# ADIS_Teensy_Arduino_Breakout_RevD.net
KiCad netlist of a schematic drawn in EAGLE
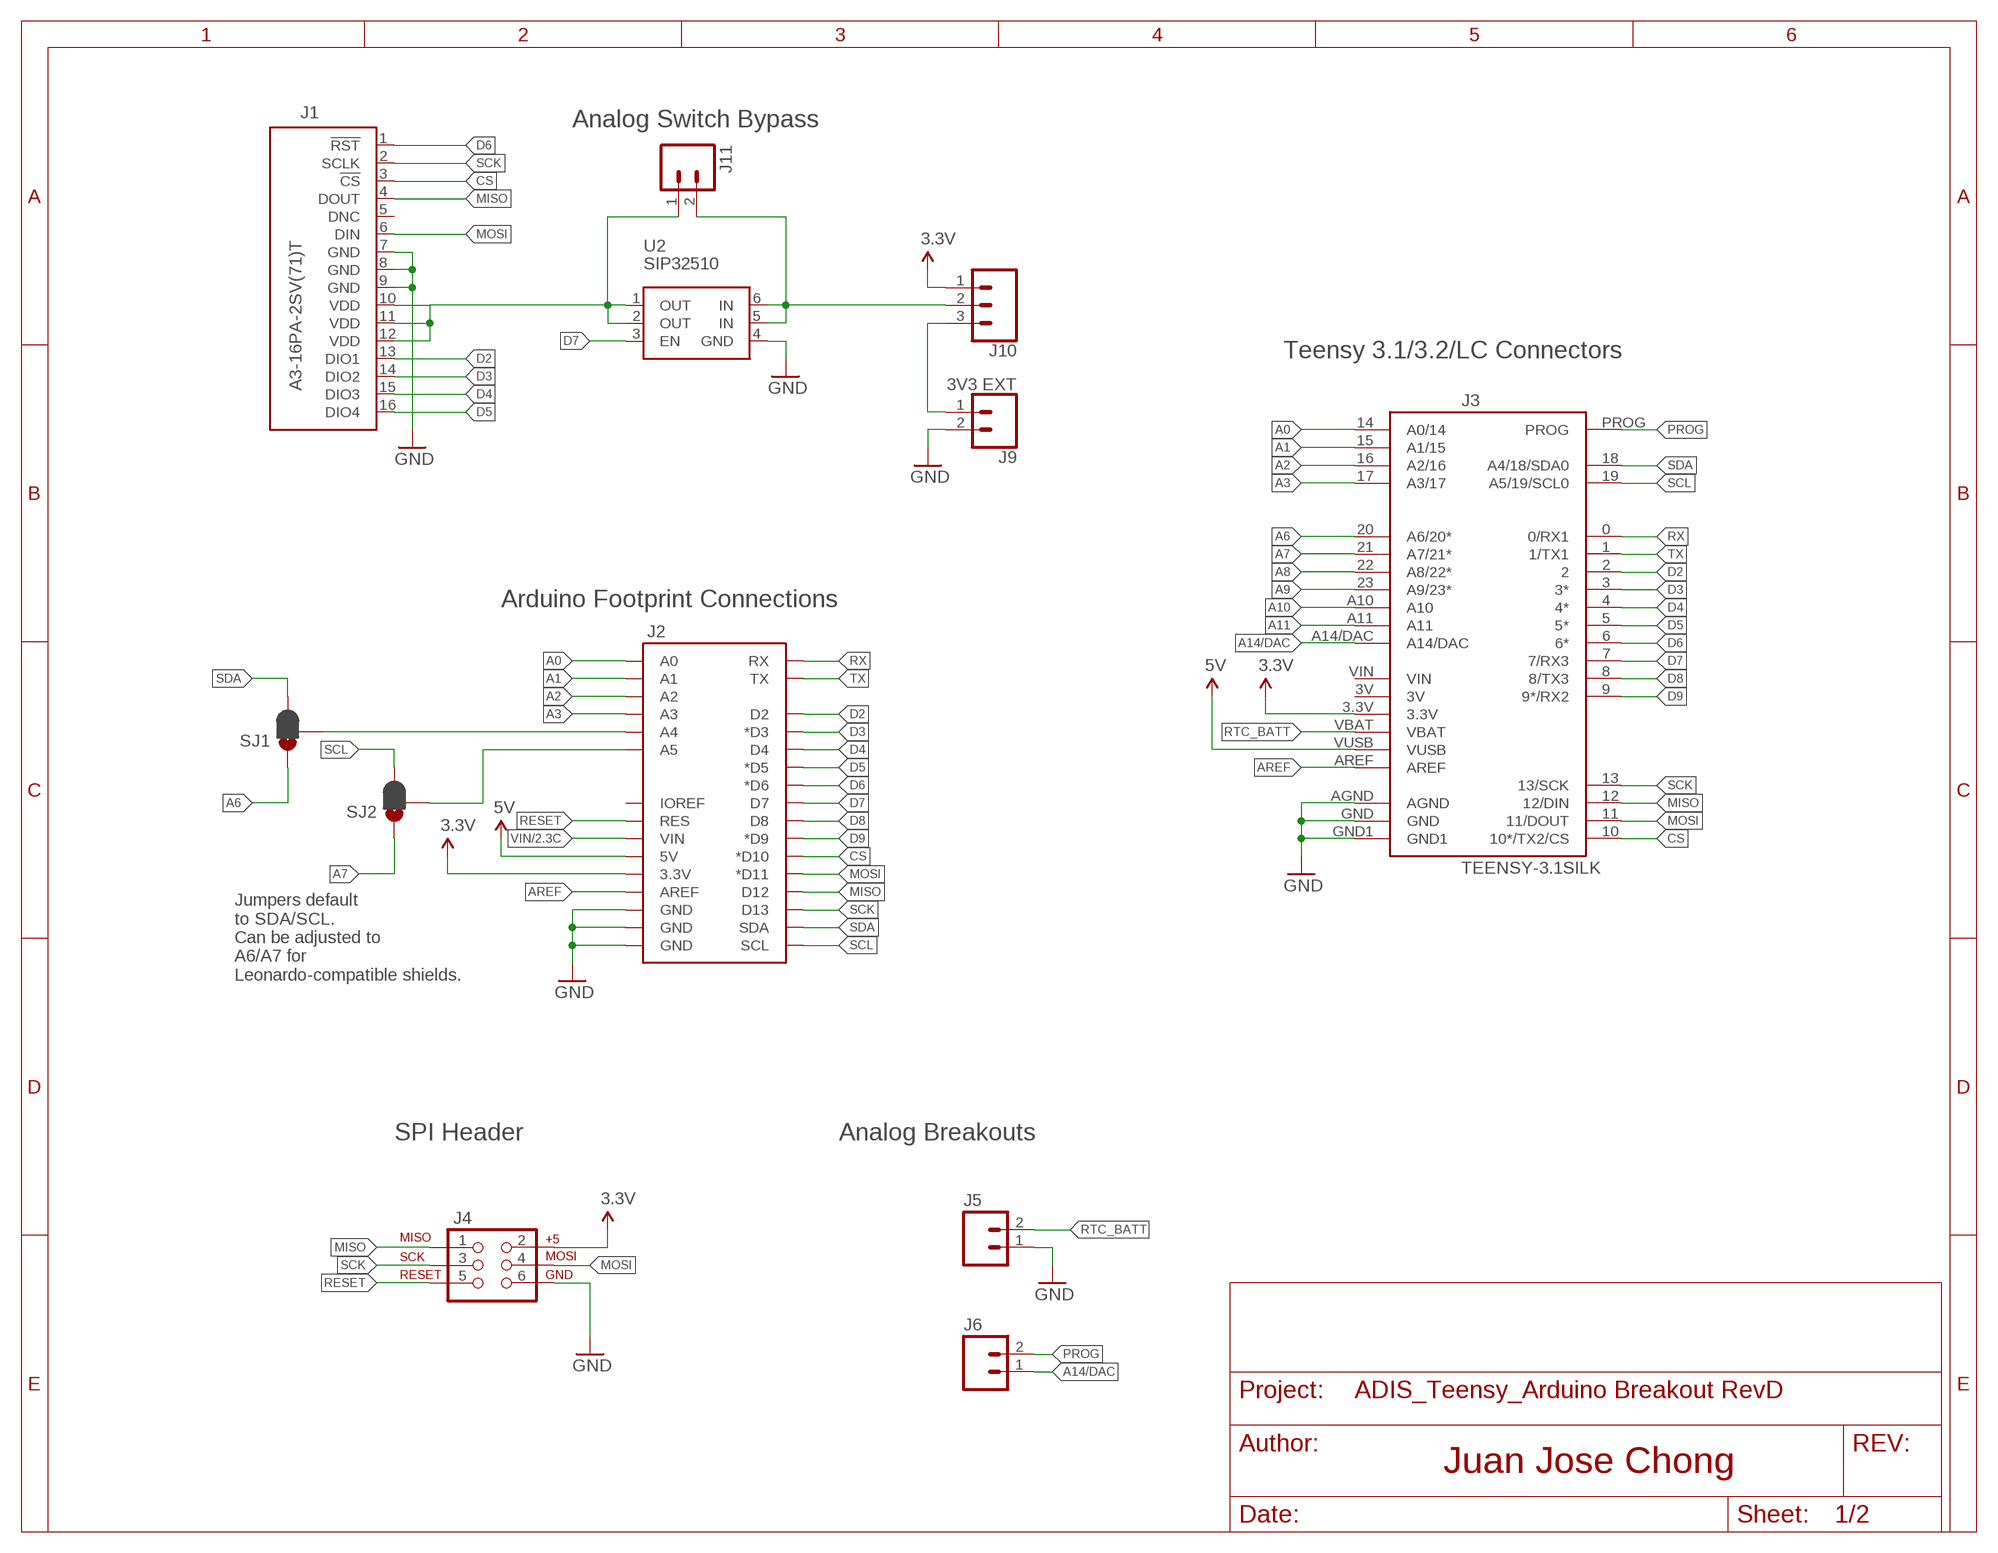
[diagram p0: schematic, sheet 1]
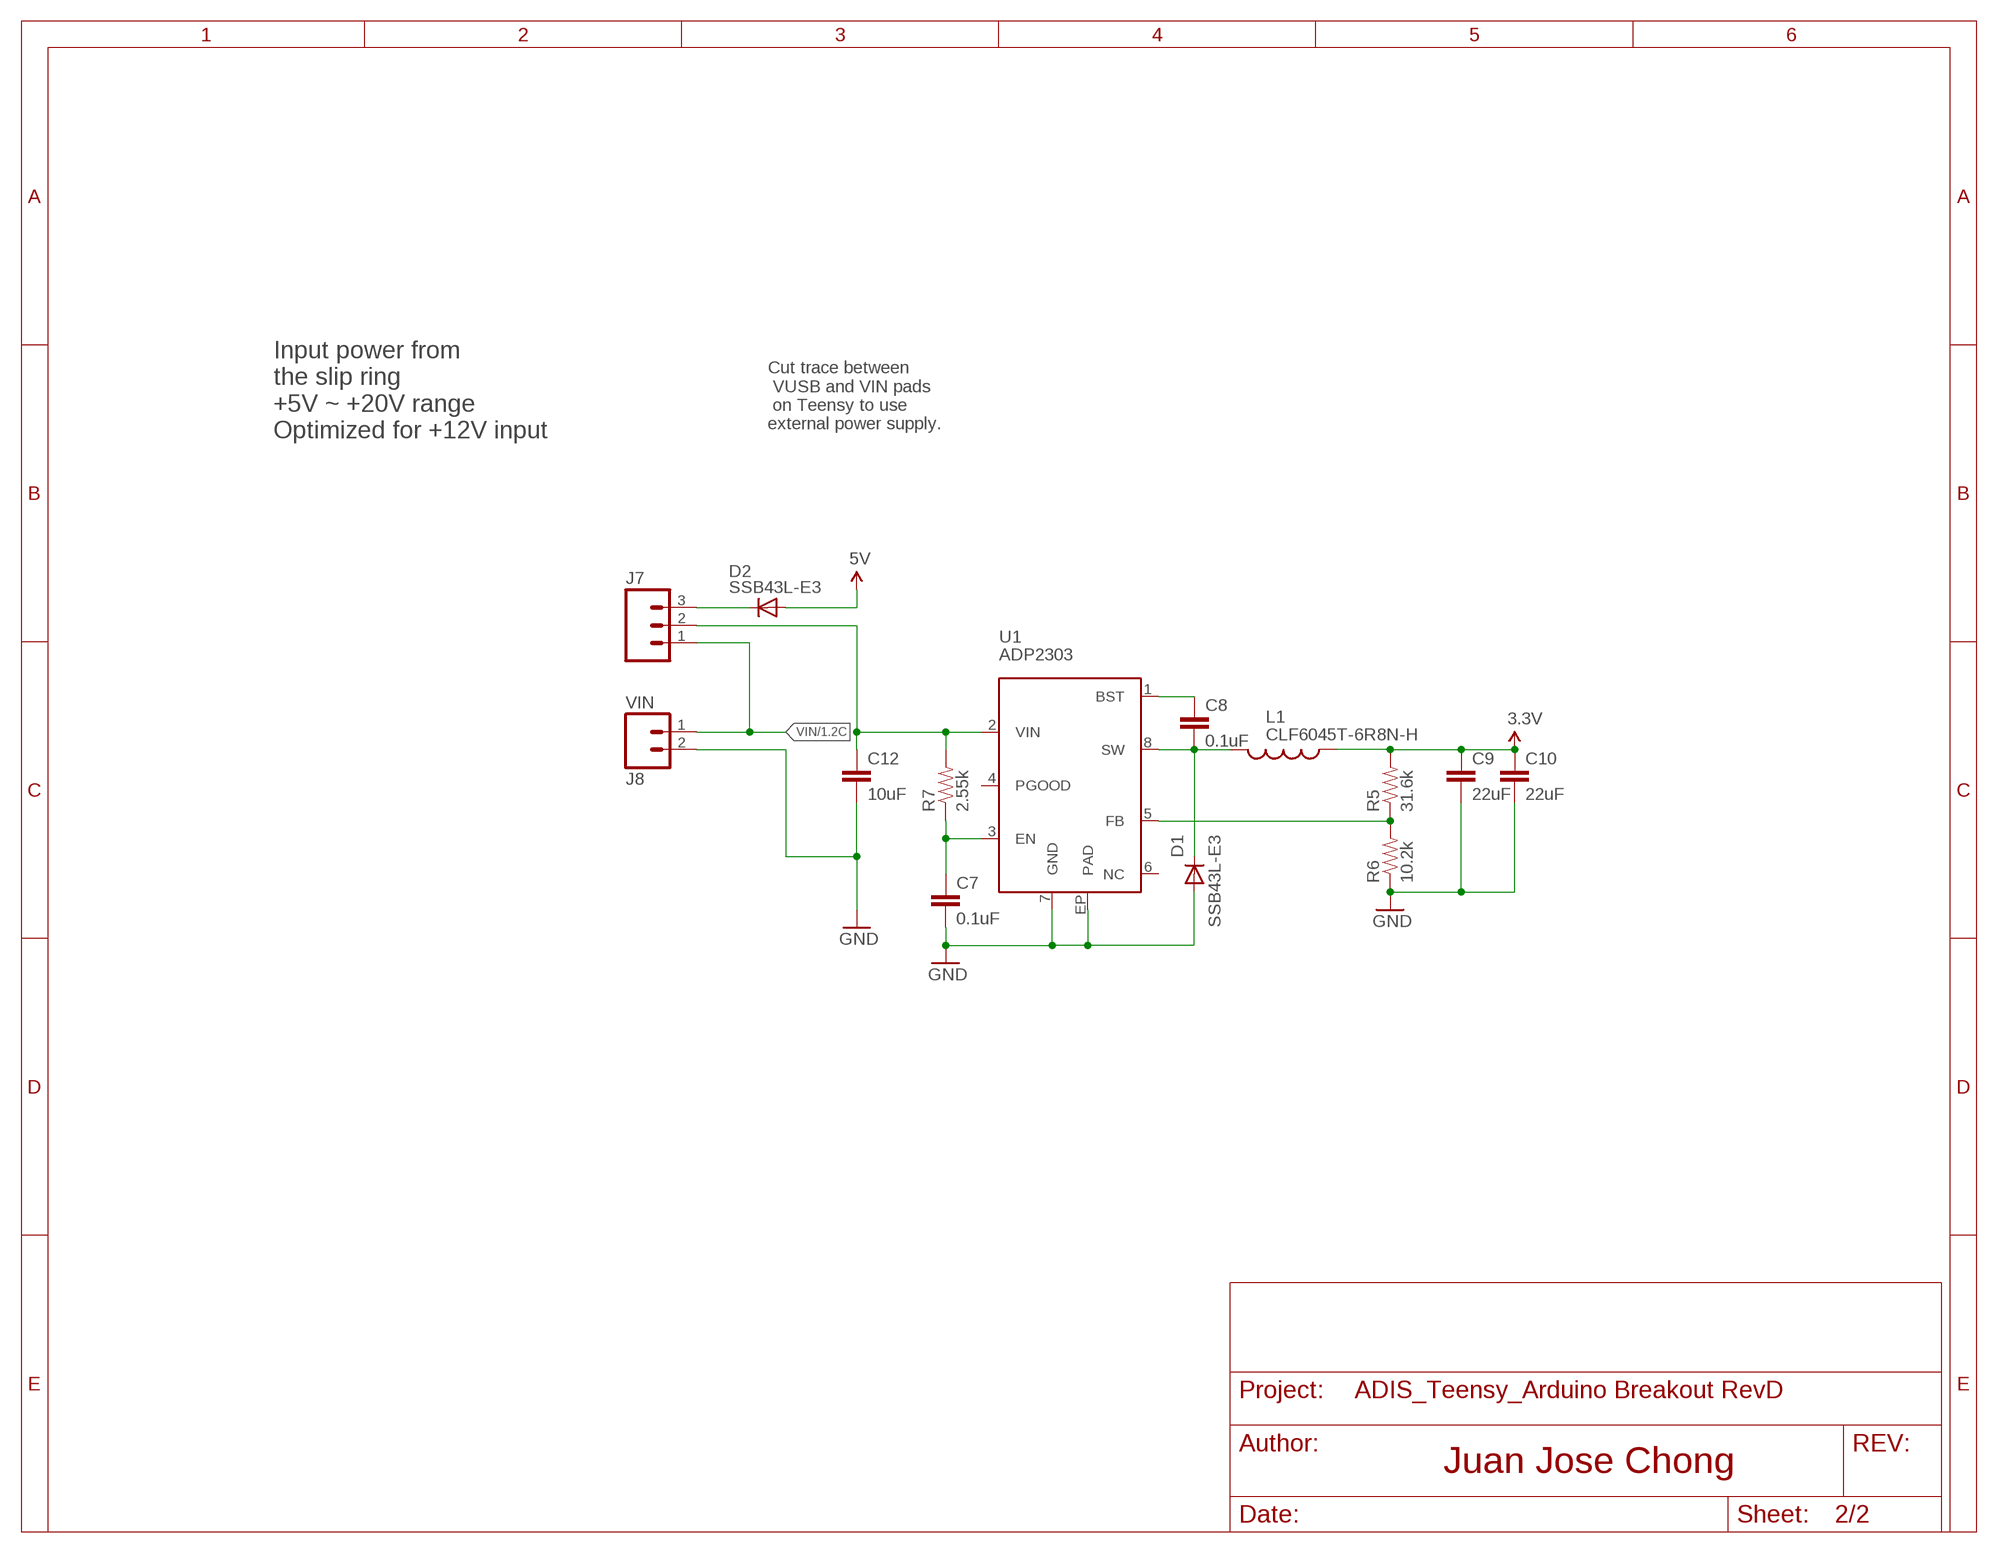
[diagram p1: schematic, sheet 2]

(export (version "E")
  (design (tool "Eeschema 10.0.6"))
  (components
    (comp (ref "J1")
      (value "A3-16PA-2SV(71)T")
      (footprint "eagle-import:A3-16PA-2SV(71)-TOP")
      (fields (field (name "PARTNO") "A3-16PA-2SV(71)"))
      (libsource (lib "eagle-import") (part "A3-16PA-2SV(71)T"))
    )
    (comp (ref "J2")
      (value "ARDUINO_R3_SHIELDUNO_R3_SHIELD_HOLES")
      (footprint "eagle-import:UNO_R3_SHIELD_HOLES")
      (libsource (lib "eagle-import") (part "ARDUINO_R3_SHIELDUNO_R3_SHIELD_HOLES"))
    )
    (comp (ref "J3")
      (value "TEENSY-3.1SILK")
      (footprint "eagle-import:TEENSY-3.1")
      (fields (field (name "PARTNO") "TEENSY32"))
      (libsource (lib "eagle-import") (part "TEENSY-3.1SILK"))
    )
    (comp (ref "J4")
      (value "AVR_SPI_PRG_6PTH")
      (footprint "eagle-import:2X3")
      (fields (field (name "PARTNO") "M20-9720345"))
      (libsource (lib "eagle-import") (part "AVR_SPI_PRG_6PTH"))
    )
    (comp (ref "J5")
      (value "M02PTH")
      (footprint "eagle-import:1X02@1")
      (libsource (lib "eagle-import") (part "M02PTH"))
    )
    (comp (ref "J6")
      (value "M02PTH")
      (footprint "eagle-import:1X02@1")
      (libsource (lib "eagle-import") (part "M02PTH"))
    )
    (comp (ref "J9")
      (value "3V3 EXT")
      (footprint "eagle-import:SCREWTERMINAL-3.5MM-2")
      (fields (field (name "PARTNO") "20020327-C021B01LF"))
      (libsource (lib "eagle-import") (part "CONN_023.5MM"))
    )
    (comp (ref "J10")
      (value "CONN_03")
      (footprint "eagle-import:1X03")
      (fields (field (name "PARTNO") "68000-103HLF"))
      (libsource (lib "eagle-import") (part "CONN_03"))
    )
    (comp (ref "J11")
      (value "M02PTH")
      (footprint "eagle-import:1X02@1")
      (libsource (lib "eagle-import") (part "M02PTH"))
    )
    (comp (ref "SJ1")
      (value "JUMPER-PAD-3-2OF3_NC_BY_PASTE")
      (footprint "eagle-import:PAD-JUMPER-3-2OF3_NC_BY_PASTE_YES_SILK_FULL_BOX")
      (libsource (lib "eagle-import") (part "JUMPER-PAD-3-2OF3_NC_BY_PASTE"))
    )
    (comp (ref "SJ2")
      (value "JUMPER-PAD-3-2OF3_NC_BY_PASTE")
      (footprint "eagle-import:PAD-JUMPER-3-2OF3_NC_BY_PASTE_YES_SILK_FULL_BOX")
      (libsource (lib "eagle-import") (part "JUMPER-PAD-3-2OF3_NC_BY_PASTE"))
    )
    (comp (ref "U2")
      (value "SIP32510")
      (footprint "eagle-import:SOT23-6")
      (fields (field (name "PARTNO") "SIP32510DT-T1-GE3"))
      (libsource (lib "eagle-import") (part "SIP32510"))
    )
    (comp (ref "C7")
      (value "0.1uF")
      (footprint "eagle-import:0603-CAP")
      (fields (field (name "PARTNO") "CL10B104KB8NNNC"))
      (libsource (lib "eagle-import") (part "CAP0603-CAP"))
    )
    (comp (ref "C8")
      (value "0.1uF")
      (footprint "eagle-import:0603-CAP")
      (fields (field (name "PARTNO") "CL10B104KB8NNNC"))
      (libsource (lib "eagle-import") (part "CAP0603-CAP"))
    )
    (comp (ref "C9")
      (value "22uF")
      (footprint "eagle-import:1210")
      (fields (field (name "PARTNO") "TLJA476M010R0600"))
      (libsource (lib "eagle-import") (part "CAP1210"))
    )
    (comp (ref "C10")
      (value "22uF")
      (footprint "eagle-import:1210")
      (fields (field (name "PARTNO") "TLJA476M010R0600"))
      (libsource (lib "eagle-import") (part "CAP1210"))
    )
    (comp (ref "C12")
      (value "10uF")
      (footprint "eagle-import:1206")
      (fields (field (name "PARTNO") "TLJA476M010R0600"))
      (libsource (lib "eagle-import") (part "CAP1206"))
    )
    (comp (ref "D1")
      (value "SSB43L-E3")
      (footprint "eagle-import:DO214AA")
      (fields (field (name "PARTNO") "SSB43L-E3/52T"))
      (libsource (lib "eagle-import") (part "DIODE-DO214AA"))
    )
    (comp (ref "D2")
      (value "SSB43L-E3")
      (footprint "eagle-import:DO214AA")
      (fields (field (name "PARTNO") "SSB43L-E3/52T"))
      (libsource (lib "eagle-import") (part "DIODE-DO214AA"))
    )
    (comp (ref "J7")
      (value "M03PTH")
      (footprint "eagle-import:1X03@1")
      (fields (field (name "PARTNO") "68000-103HLF"))
      (libsource (lib "eagle-import") (part "M03PTH"))
    )
    (comp (ref "J8")
      (value "VIN")
      (footprint "eagle-import:SCREWTERMINAL-3.5MM-2@1")
      (fields (field (name "PARTNO") "20020327-C021B01LF"))
      (libsource (lib "eagle-import") (part "M023.5MM"))
    )
    (comp (ref "L1")
      (value "CLF6045T-6R8N-H")
      (footprint "eagle-import:CLF6045-H")
      (libsource (lib "eagle-import") (part "CLF6045T-6R8N-H"))
    )
    (comp (ref "R5")
      (value "31.6k")
      (footprint "eagle-import:0603-RES")
      (fields (field (name "PARTNO") "ERJ-3EKF3162V"))
      (libsource (lib "eagle-import") (part "RESISTOR0603-RES"))
    )
    (comp (ref "R6")
      (value "10.2k")
      (footprint "eagle-import:0603-RES")
      (fields (field (name "PARTNO") "ERJ-3EKF1022V"))
      (libsource (lib "eagle-import") (part "RESISTOR0603-RES"))
    )
    (comp (ref "R7")
      (value "2.55k")
      (footprint "eagle-import:0603-RES")
      (fields (field (name "PARTNO") "ERJ-3EKF2551V"))
      (libsource (lib "eagle-import") (part "RESISTOR0603-RES"))
    )
    (comp (ref "U1")
      (value "ADP2303")
      (footprint "eagle-import:SOIC-8-PAD")
      (fields (field (name "PARTNO") "ADP2303ARDZ"))
      (libsource (lib "eagle-import") (part "ADP2303"))
    )
  )
  (nets
    (net (code "1") (name "3.3V") (class "Default")
      (node (ref "C10") (pin "1") (pinfunction "1_1") (pintype "passive"))
      (node (ref "C9") (pin "1") (pinfunction "1_1") (pintype "passive"))
      (node (ref "J10") (pin "1") (pinfunction "1_1") (pintype "passive"))
      (node (ref "J2") (pin "3.3V") (pinfunction "3.3V_3.3V") (pintype "bidirectional"))
      (node (ref "J3") (pin "3.3V") (pinfunction "3.3V_3.3V") (pintype "bidirectional"))
      (node (ref "J4") (pin "2") (pinfunction "2_2") (pintype "passive"))
      (node (ref "L1") (pin "P$1") (pinfunction "1_P$1") (pintype "passive"))
      (node (ref "R5") (pin "2") (pinfunction "2_2") (pintype "passive"))
    )
    (net (code "2") (name "5V") (class "Default")
      (node (ref "D2") (pin "A") (pinfunction "A_A") (pintype "passive"))
      (node (ref "J2") (pin "5V") (pinfunction "5V_5V") (pintype "bidirectional"))
      (node (ref "J3") (pin "VUSB") (pinfunction "VUSB_VUSB") (pintype "bidirectional"))
    )
    (net (code "3") (name "A0") (class "Default")
      (node (ref "J2") (pin "A0") (pinfunction "A0_A0") (pintype "bidirectional"))
      (node (ref "J3") (pin "14") (pinfunction "A0/14_14") (pintype "bidirectional"))
    )
    (net (code "4") (name "A1") (class "Default")
      (node (ref "J2") (pin "A1") (pinfunction "A1_A1") (pintype "bidirectional"))
      (node (ref "J3") (pin "15") (pinfunction "A1/15_15") (pintype "bidirectional"))
    )
    (net (code "5") (name "A2") (class "Default")
      (node (ref "J2") (pin "A2") (pinfunction "A2_A2") (pintype "bidirectional"))
      (node (ref "J3") (pin "16") (pinfunction "A2/16_16") (pintype "bidirectional"))
    )
    (net (code "6") (name "A3") (class "Default")
      (node (ref "J2") (pin "A3") (pinfunction "A3_A3") (pintype "bidirectional"))
      (node (ref "J3") (pin "17") (pinfunction "A3/17_17") (pintype "bidirectional"))
    )
    (net (code "7") (name "A6") (class "Default")
      (node (ref "J3") (pin "20") (pinfunction "A6/20*_20") (pintype "bidirectional"))
      (node (ref "SJ1") (pin "1") (pinfunction "1_1") (pintype "passive"))
    )
    (net (code "8") (name "A7") (class "Default")
      (node (ref "J3") (pin "21") (pinfunction "A7/21*_21") (pintype "bidirectional"))
      (node (ref "SJ2") (pin "1") (pinfunction "1_1") (pintype "passive"))
    )
    (net (code "9") (name "A8") (class "Default")
      (node (ref "J3") (pin "22") (pinfunction "A8/22*_22") (pintype "bidirectional"))
    )
    (net (code "10") (name "A9") (class "Default")
      (node (ref "J3") (pin "23") (pinfunction "A9/23*_23") (pintype "bidirectional"))
    )
    (net (code "11") (name "A10") (class "Default")
      (node (ref "J3") (pin "A10") (pinfunction "A10_A10") (pintype "bidirectional"))
    )
    (net (code "12") (name "A11") (class "Default")
      (node (ref "J3") (pin "A11") (pinfunction "A11_A11") (pintype "bidirectional"))
    )
    (net (code "13") (name "A14{slash}DAC") (class "Default")
      (node (ref "J3") (pin "A14/DAC") (pinfunction "A14/DAC_A14/DAC") (pintype "bidirectional"))
      (node (ref "J6") (pin "1") (pinfunction "1_1") (pintype "passive"))
    )
    (net (code "14") (name "AREF") (class "Default")
      (node (ref "J2") (pin "AREF") (pinfunction "AREF_AREF") (pintype "bidirectional"))
      (node (ref "J3") (pin "AREF") (pinfunction "AREF_AREF") (pintype "bidirectional"))
    )
    (net (code "15") (name "CS") (class "Default")
      (node (ref "J1") (pin "3") (pinfunction "~{CS}_3") (pintype "bidirectional"))
      (node (ref "J2") (pin "D10") (pinfunction "*D10_D10") (pintype "bidirectional"))
      (node (ref "J3") (pin "10") (pinfunction "10*/TX2/CS_10") (pintype "bidirectional"))
    )
    (net (code "16") (name "D2") (class "Default")
      (node (ref "J1") (pin "13") (pinfunction "DIO1_13") (pintype "bidirectional"))
      (node (ref "J2") (pin "D2") (pinfunction "D2_D2") (pintype "bidirectional"))
      (node (ref "J3") (pin "2") (pinfunction "2_2") (pintype "bidirectional"))
    )
    (net (code "17") (name "D3") (class "Default")
      (node (ref "J1") (pin "14") (pinfunction "DIO2_14") (pintype "bidirectional"))
      (node (ref "J2") (pin "D3") (pinfunction "*D3_D3") (pintype "bidirectional"))
      (node (ref "J3") (pin "3") (pinfunction "3*_3") (pintype "bidirectional"))
    )
    (net (code "18") (name "D4") (class "Default")
      (node (ref "J1") (pin "15") (pinfunction "DIO3_15") (pintype "bidirectional"))
      (node (ref "J2") (pin "D4") (pinfunction "D4_D4") (pintype "bidirectional"))
      (node (ref "J3") (pin "4") (pinfunction "4*_4") (pintype "bidirectional"))
    )
    (net (code "19") (name "D5") (class "Default")
      (node (ref "J1") (pin "16") (pinfunction "DIO4_16") (pintype "bidirectional"))
      (node (ref "J2") (pin "D5") (pinfunction "*D5_D5") (pintype "bidirectional"))
      (node (ref "J3") (pin "5") (pinfunction "5*_5") (pintype "bidirectional"))
    )
    (net (code "20") (name "D6") (class "Default")
      (node (ref "J1") (pin "1") (pinfunction "~{RST}_1") (pintype "bidirectional"))
      (node (ref "J2") (pin "D6") (pinfunction "*D6_D6") (pintype "bidirectional"))
      (node (ref "J3") (pin "6") (pinfunction "6*_6") (pintype "bidirectional"))
    )
    (net (code "21") (name "D7") (class "Default")
      (node (ref "J2") (pin "D7") (pinfunction "D7_D7") (pintype "bidirectional"))
      (node (ref "J3") (pin "7") (pinfunction "7/RX3_7") (pintype "bidirectional"))
      (node (ref "U2") (pin "3") (pinfunction "EN_3") (pintype "bidirectional"))
    )
    (net (code "22") (name "D8") (class "Default")
      (node (ref "J2") (pin "D8") (pinfunction "D8_D8") (pintype "bidirectional"))
      (node (ref "J3") (pin "8") (pinfunction "8/TX3_8") (pintype "bidirectional"))
    )
    (net (code "23") (name "D9") (class "Default")
      (node (ref "J2") (pin "D9") (pinfunction "*D9_D9") (pintype "bidirectional"))
      (node (ref "J3") (pin "9") (pinfunction "9*/RX2_9") (pintype "bidirectional"))
    )
    (net (code "24") (name "GND") (class "Default")
      (node (ref "C10") (pin "2") (pinfunction "2_2") (pintype "passive"))
      (node (ref "C12") (pin "2") (pinfunction "2_2") (pintype "passive"))
      (node (ref "C7") (pin "2") (pinfunction "2_2") (pintype "passive"))
      (node (ref "C9") (pin "2") (pinfunction "2_2") (pintype "passive"))
      (node (ref "D1") (pin "A") (pinfunction "A_A") (pintype "passive"))
      (node (ref "J1") (pin "7") (pinfunction "GND_7") (pintype "bidirectional"))
      (node (ref "J1") (pin "8") (pinfunction "GND_8") (pintype "bidirectional"))
      (node (ref "J1") (pin "9") (pinfunction "GND_9") (pintype "bidirectional"))
      (node (ref "J2") (pin "GND@0") (pinfunction "GND_GND@0") (pintype "bidirectional"))
      (node (ref "J2") (pin "GND@1") (pinfunction "GND_GND@1") (pintype "bidirectional"))
      (node (ref "J2") (pin "GND@2") (pinfunction "GND_GND@2") (pintype "bidirectional"))
      (node (ref "J3") (pin "AGND") (pinfunction "AGND_AGND") (pintype "bidirectional"))
      (node (ref "J3") (pin "GND") (pinfunction "GND_GND") (pintype "bidirectional"))
      (node (ref "J3") (pin "GND1") (pinfunction "GND1_GND1") (pintype "bidirectional"))
      (node (ref "J4") (pin "6") (pinfunction "6_6") (pintype "passive"))
      (node (ref "J5") (pin "1") (pinfunction "1_1") (pintype "passive"))
      (node (ref "J8") (pin "2") (pinfunction "2_2") (pintype "passive"))
      (node (ref "J9") (pin "2") (pinfunction "2_2") (pintype "passive"))
      (node (ref "R6") (pin "1") (pinfunction "1_1") (pintype "passive"))
      (node (ref "U1") (pin "7") (pinfunction "GND_7") (pintype "bidirectional"))
      (node (ref "U1") (pin "EP") (pinfunction "PAD_EP") (pintype "bidirectional"))
      (node (ref "U2") (pin "4") (pinfunction "GND_4") (pintype "bidirectional"))
    )
    (net (code "25") (name "MISO") (class "Default")
      (node (ref "J1") (pin "4") (pinfunction "DOUT_4") (pintype "bidirectional"))
      (node (ref "J2") (pin "D12") (pinfunction "D12_D12") (pintype "bidirectional"))
      (node (ref "J3") (pin "12") (pinfunction "12/DIN_12") (pintype "bidirectional"))
      (node (ref "J4") (pin "1") (pinfunction "1_1") (pintype "passive"))
    )
    (net (code "26") (name "MOSI") (class "Default")
      (node (ref "J1") (pin "6") (pinfunction "DIN_6") (pintype "bidirectional"))
      (node (ref "J2") (pin "D11") (pinfunction "*D11_D11") (pintype "bidirectional"))
      (node (ref "J3") (pin "11") (pinfunction "11/DOUT_11") (pintype "bidirectional"))
      (node (ref "J4") (pin "4") (pinfunction "4_4") (pintype "passive"))
    )
    (net (code "27") (name "Net-(D2-PadC)") (class "Default")
      (node (ref "D2") (pin "C") (pinfunction "C_C") (pintype "passive"))
      (node (ref "J7") (pin "3") (pinfunction "3_3") (pintype "passive"))
    )
    (net (code "28") (name "Net-(J1-VDD-Pad10)") (class "Default")
      (node (ref "J1") (pin "10") (pinfunction "VDD_10") (pintype "bidirectional"))
      (node (ref "J1") (pin "11") (pinfunction "VDD_11") (pintype "bidirectional"))
      (node (ref "J1") (pin "12") (pinfunction "VDD_12") (pintype "bidirectional"))
      (node (ref "J11") (pin "1") (pinfunction "1_1") (pintype "passive"))
      (node (ref "U2") (pin "1") (pinfunction "OUT_1") (pintype "bidirectional"))
      (node (ref "U2") (pin "2") (pinfunction "OUT_2") (pintype "bidirectional"))
    )
    (net (code "29") (name "Net-(J2-PadA4)") (class "Default")
      (node (ref "J2") (pin "A4") (pinfunction "A4_A4") (pintype "bidirectional"))
      (node (ref "SJ1") (pin "2") (pinfunction "2_2") (pintype "passive"))
    )
    (net (code "30") (name "Net-(J2-PadA5)") (class "Default")
      (node (ref "J2") (pin "A5") (pinfunction "A5_A5") (pintype "bidirectional"))
      (node (ref "SJ2") (pin "2") (pinfunction "2_2") (pintype "passive"))
    )
    (net (code "31") (name "Net-(J10-Pad2)") (class "Default")
      (node (ref "J10") (pin "2") (pinfunction "2_2") (pintype "passive"))
      (node (ref "J11") (pin "2") (pinfunction "2_2") (pintype "passive"))
      (node (ref "U2") (pin "5") (pinfunction "IN_5") (pintype "bidirectional"))
      (node (ref "U2") (pin "6") (pinfunction "IN_6") (pintype "bidirectional"))
    )
    (net (code "32") (name "Net-(J10-Pad3)") (class "Default")
      (node (ref "J10") (pin "3") (pinfunction "3_3") (pintype "passive"))
      (node (ref "J9") (pin "1") (pinfunction "1_1") (pintype "passive"))
    )
    (net (code "33") (name "Net-(L1-2)") (class "Default")
      (node (ref "C8") (pin "2") (pinfunction "2_2") (pintype "passive"))
      (node (ref "D1") (pin "C") (pinfunction "C_C") (pintype "passive"))
      (node (ref "L1") (pin "P$2") (pinfunction "2_P$2") (pintype "passive"))
      (node (ref "U1") (pin "8") (pinfunction "SW_8") (pintype "bidirectional"))
    )
    (net (code "34") (name "Net-(U1-BST)") (class "Default")
      (node (ref "C8") (pin "1") (pinfunction "1_1") (pintype "passive"))
      (node (ref "U1") (pin "1") (pinfunction "BST_1") (pintype "bidirectional"))
    )
    (net (code "35") (name "Net-(U1-EN)") (class "Default")
      (node (ref "C7") (pin "1") (pinfunction "1_1") (pintype "passive"))
      (node (ref "R7") (pin "1") (pinfunction "1_1") (pintype "passive"))
      (node (ref "U1") (pin "3") (pinfunction "EN_3") (pintype "bidirectional"))
    )
    (net (code "36") (name "Net-(U1-FB)") (class "Default")
      (node (ref "R5") (pin "1") (pinfunction "1_1") (pintype "passive"))
      (node (ref "R6") (pin "2") (pinfunction "2_2") (pintype "passive"))
      (node (ref "U1") (pin "5") (pinfunction "FB_5") (pintype "bidirectional"))
    )
    (net (code "37") (name "Net-(U1-VIN)") (class "Default")
      (node (ref "C12") (pin "1") (pinfunction "1_1") (pintype "passive"))
      (node (ref "J7") (pin "2") (pinfunction "2_2") (pintype "passive"))
      (node (ref "R7") (pin "2") (pinfunction "2_2") (pintype "passive"))
      (node (ref "U1") (pin "2") (pinfunction "VIN_2") (pintype "bidirectional"))
    )
    (net (code "38") (name "PROG") (class "Default")
      (node (ref "J3") (pin "PROG") (pinfunction "PROG_PROG") (pintype "bidirectional"))
      (node (ref "J6") (pin "2") (pinfunction "2_2") (pintype "passive"))
    )
    (net (code "39") (name "RESET") (class "Default")
      (node (ref "J2") (pin "RES") (pinfunction "RES_RES") (pintype "bidirectional"))
      (node (ref "J4") (pin "5") (pinfunction "5_5") (pintype "passive"))
    )
    (net (code "40") (name "RTC_BATT") (class "Default")
      (node (ref "J3") (pin "VBAT") (pinfunction "VBAT_VBAT") (pintype "bidirectional"))
      (node (ref "J5") (pin "2") (pinfunction "2_2") (pintype "passive"))
    )
    (net (code "41") (name "RX") (class "Default")
      (node (ref "J2") (pin "RX") (pinfunction "RX_RX") (pintype "bidirectional"))
      (node (ref "J3") (pin "0") (pinfunction "0/RX1_0") (pintype "bidirectional"))
    )
    (net (code "42") (name "SCK") (class "Default")
      (node (ref "J1") (pin "2") (pinfunction "SCLK_2") (pintype "bidirectional"))
      (node (ref "J2") (pin "D13") (pinfunction "D13_D13") (pintype "bidirectional"))
      (node (ref "J3") (pin "13") (pinfunction "13/SCK_13") (pintype "bidirectional"))
      (node (ref "J4") (pin "3") (pinfunction "3_3") (pintype "passive"))
    )
    (net (code "43") (name "SCL") (class "Default")
      (node (ref "J2") (pin "SCL") (pinfunction "SCL_SCL") (pintype "bidirectional"))
      (node (ref "J3") (pin "19") (pinfunction "A5/19/SCL0_19") (pintype "bidirectional"))
      (node (ref "SJ2") (pin "3") (pinfunction "3_3") (pintype "passive"))
    )
    (net (code "44") (name "SDA") (class "Default")
      (node (ref "J2") (pin "SDA") (pinfunction "SDA_SDA") (pintype "bidirectional"))
      (node (ref "J3") (pin "18") (pinfunction "A4/18/SDA0_18") (pintype "bidirectional"))
      (node (ref "SJ1") (pin "3") (pinfunction "3_3") (pintype "passive"))
    )
    (net (code "45") (name "TX") (class "Default")
      (node (ref "J2") (pin "TX") (pinfunction "TX_TX") (pintype "bidirectional"))
      (node (ref "J3") (pin "1") (pinfunction "1/TX1_1") (pintype "bidirectional"))
    )
    (net (code "46") (name "VIN") (class "Default")
      (node (ref "J2") (pin "VIN") (pinfunction "VIN_VIN") (pintype "bidirectional"))
      (node (ref "J7") (pin "1") (pinfunction "1_1") (pintype "passive"))
      (node (ref "J8") (pin "1") (pinfunction "1_1") (pintype "passive"))
    )
    (net (code "47") (name "unconnected-(J1-DNC-Pad5)") (class "Default")
      (node (ref "J1") (pin "5") (pinfunction "DNC_5") (pintype "bidirectional"))
    )
    (net (code "48") (name "unconnected-(J2-PadIOREF)") (class "Default")
      (node (ref "J2") (pin "IOREF") (pinfunction "IOREF_IOREF") (pintype "bidirectional"))
    )
    (net (code "49") (name "unconnected-(J3-Pad3V)") (class "Default")
      (node (ref "J3") (pin "3V") (pinfunction "3V_3V") (pintype "bidirectional"))
    )
    (net (code "50") (name "unconnected-(J3-PadVIN)") (class "Default")
      (node (ref "J3") (pin "VIN") (pinfunction "VIN_VIN") (pintype "bidirectional"))
    )
    (net (code "51") (name "unconnected-(U1-NC-Pad6)") (class "Default")
      (node (ref "U1") (pin "6") (pinfunction "NC_6") (pintype "bidirectional"))
    )
    (net (code "52") (name "unconnected-(U1-PGOOD-Pad4)") (class "Default")
      (node (ref "U1") (pin "4") (pinfunction "PGOOD_4") (pintype "bidirectional"))
    )
  )
)
